# FPGA_USB.net
KiCad netlist of a schematic drawn in Altium Designer
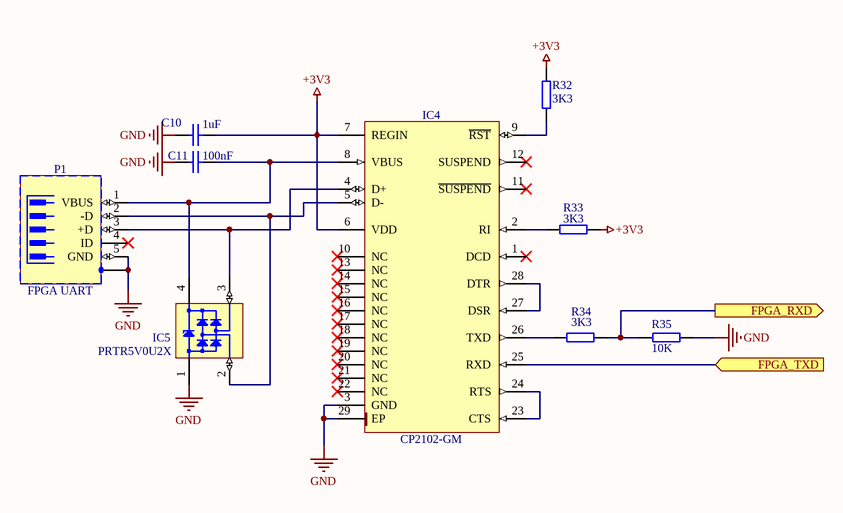
[diagram p0: FPGA_USB.SchDoc]

(export (version "E")
  (design (tool "Eeschema 10.0.6"))
  (components
    (comp (ref "C10")
      (value "1uF")
      (footprint "CC1608-0603")
      (description "Capacitor")
      (fields
        (field (name "TOLERANCE") "±10%")
        (field (name "VOLTAGE") "25V")
        (field (name "PUBLISHER") "Altium Limited")
      )
      (libsource (lib "wr_switch") (part "Cap"))
    )
    (comp (ref "C11")
      (value "100nF")
      (footprint "CC1608-0603")
      (description "Capacitor")
      (fields
        (field (name "TOLERANCE") "±10%")
        (field (name "VOLTAGE") "16V")
        (field (name "PUBLISHER") "Altium Limited")
      )
      (libsource (lib "wr_switch") (part "Cap"))
    )
    (comp (ref "IC4")
      (value "CP2102-GM")
      (footprint "7S_WR:QFN50P500X500X100-29N-S335")
      (description "Single-Chip USB to UART Bridge")
      (fields (field (name "MANUFACTURER") "SILICON LABS") (field (name "AUTHOR") "CERN DEM JLC"))
      (libsource (lib "wr_switch") (part "CP2102-GM"))
    )
    (comp (ref "IC5")
      (value "PRTR5V0U2X")
      (footprint "7S_WR:SOT190P230X110-4N")
      (description "Ultra Low Capacitance Double Rail-to-Rail ESD Protection Diode")
      (fields
        (field (name "VOLTAGE") "5.5V")
        (field (name "MANUFACTURER") "PHILIPS NXP")
        (field (name "AUTHOR") "CERN DEM JLC")
      )
      (libsource (lib "wr_switch") (part "PRTR5V0U2X"))
    )
    (comp (ref "P1")
      (value "FPGA UART")
      (footprint "7S_WR:TYCO_1734035-1")
      (description "5 Pin + 1 Shield Mini USB Type B Receptacle")
      (fields
        (field (name "PART NUMBER") "TYCO_1734035-1")
        (field (name "MANUFACTURER") "TYCO ELECTRONICS")
        (field (name "AUTHOR") "CERN DEM JLC")
      )
      (libsource (lib "wr_switch") (part "TYCO_1734035-1"))
    )
    (comp (ref "R32")
      (value "3K3")
      (footprint "0603")
      (description "SMD Resistor")
      (fields (field (name "TOLERANCE") "±1%"))
      (libsource (lib "wr_switch") (part "RES_SMD"))
    )
    (comp (ref "R33")
      (value "3K3")
      (footprint "0603")
      (description "SMD Resistor")
      (fields (field (name "TOLERANCE") "±1%"))
      (libsource (lib "wr_switch") (part "RES_SMD"))
    )
    (comp (ref "R34")
      (value "3K3")
      (footprint "0603")
      (description "SMD Resistor")
      (fields (field (name "TOLERANCE") "±1%"))
      (libsource (lib "wr_switch") (part "RES_SMD"))
    )
    (comp (ref "R35")
      (value "10K")
      (footprint "0603")
      (description "SMD Resistor")
      (fields (field (name "TOLERANCE") "±1%"))
      (libsource (lib "wr_switch") (part "RES_SMD"))
    )
  )
  (nets
    (net (code "1") (name "+3V3") (class "Default")
      (node (ref "C10") (pin "2") (pinfunction "2_2") (pintype "passive"))
      (node (ref "IC4") (pin "6") (pinfunction "VDD_6") (pintype "power_in"))
      (node (ref "IC4") (pin "7") (pinfunction "REGIN_7") (pintype "power_in"))
      (node (ref "R32") (pin "2") (pinfunction "2_2") (pintype "passive"))
      (node (ref "R33") (pin "2") (pinfunction "2_2") (pintype "passive"))
    )
    (net (code "2") (name "/FPGA_RXD") (class "Default")
      (node (ref "R34") (pin "2") (pinfunction "2_2") (pintype "passive"))
      (node (ref "R35") (pin "2") (pinfunction "2_2") (pintype "passive"))
    )
    (net (code "3") (name "/FPGA_TXD") (class "Default")
      (node (ref "IC4") (pin "25") (pinfunction "RXD_25") (pintype "input"))
    )
    (net (code "4") (name "GND") (class "Default")
      (node (ref "C10") (pin "1") (pinfunction "1_1") (pintype "passive"))
      (node (ref "C11") (pin "2") (pinfunction "2_2") (pintype "passive"))
      (node (ref "IC4") (pin "29") (pinfunction "EP_29") (pintype "power_in"))
      (node (ref "IC4") (pin "3") (pinfunction "GND_3") (pintype "power_in"))
      (node (ref "IC5") (pin "1") (pinfunction "GND_1") (pintype "power_in"))
      (node (ref "P1") (pin "5") (pinfunction "GND_5") (pintype "bidirectional"))
      (node (ref "P1") (pin "6") (pinfunction "SH_6") (pintype "power_in"))
      (node (ref "R35") (pin "1") (pinfunction "1_1") (pintype "passive"))
    )
    (net (code "5") (name "Net-(IC4-CTS)") (class "Default")
      (node (ref "IC4") (pin "23") (pinfunction "CTS_23") (pintype "input"))
      (node (ref "IC4") (pin "24") (pinfunction "RTS_24") (pintype "output"))
    )
    (net (code "6") (name "Net-(IC4-D+)") (class "Default")
      (node (ref "IC4") (pin "4") (pinfunction "D+_4") (pintype "bidirectional"))
      (node (ref "IC5") (pin "3") (pinfunction "I/O2_3") (pintype "bidirectional"))
      (node (ref "P1") (pin "3") (pinfunction "+D_3") (pintype "bidirectional"))
    )
    (net (code "7") (name "Net-(IC4-D-)") (class "Default")
      (node (ref "IC4") (pin "5") (pinfunction "D-_5") (pintype "bidirectional"))
      (node (ref "IC5") (pin "2") (pinfunction "I/O1_2") (pintype "bidirectional"))
      (node (ref "P1") (pin "2") (pinfunction "-D_2") (pintype "bidirectional"))
    )
    (net (code "8") (name "Net-(IC4-DSR)") (class "Default")
      (node (ref "IC4") (pin "27") (pinfunction "DSR_27") (pintype "input"))
      (node (ref "IC4") (pin "28") (pinfunction "DTR_28") (pintype "output"))
    )
    (net (code "9") (name "Net-(IC4-RI)") (class "Default")
      (node (ref "IC4") (pin "2") (pinfunction "RI_2") (pintype "input"))
      (node (ref "R33") (pin "1") (pinfunction "1_1") (pintype "passive"))
    )
    (net (code "10") (name "Net-(IC4-TXD)") (class "Default")
      (node (ref "IC4") (pin "26") (pinfunction "TXD_26") (pintype "output"))
      (node (ref "R34") (pin "1") (pinfunction "1_1") (pintype "passive"))
    )
    (net (code "11") (name "Net-(IC4-VBUS)") (class "Default")
      (node (ref "C11") (pin "1") (pinfunction "1_1") (pintype "passive"))
      (node (ref "IC4") (pin "8") (pinfunction "VBUS_8") (pintype "input"))
      (node (ref "IC5") (pin "4") (pinfunction "VCC_4") (pintype "power_in"))
      (node (ref "P1") (pin "1") (pinfunction "VBUS_1") (pintype "bidirectional"))
    )
    (net (code "12") (name "Net-(IC4-~{RST})") (class "Default")
      (node (ref "IC4") (pin "9") (pinfunction "~{RST}_9") (pintype "bidirectional"))
      (node (ref "R32") (pin "1") (pinfunction "1_1") (pintype "passive"))
    )
    (net (code "13") (name "unconnected-(IC4-DCD-Pad1)") (class "Default")
      (node (ref "IC4") (pin "1") (pinfunction "DCD_1") (pintype "input+no_connect"))
    )
    (net (code "14") (name "unconnected-(IC4-NC-Pad10)") (class "Default")
      (node (ref "IC4") (pin "10") (pinfunction "NC_10") (pintype "passive+no_connect"))
    )
    (net (code "15") (name "unconnected-(IC4-NC-Pad13)") (class "Default")
      (node (ref "IC4") (pin "13") (pinfunction "NC_13") (pintype "passive+no_connect"))
    )
    (net (code "16") (name "unconnected-(IC4-NC-Pad14)") (class "Default")
      (node (ref "IC4") (pin "14") (pinfunction "NC_14") (pintype "passive+no_connect"))
    )
    (net (code "17") (name "unconnected-(IC4-NC-Pad15)") (class "Default")
      (node (ref "IC4") (pin "15") (pinfunction "NC_15") (pintype "passive+no_connect"))
    )
    (net (code "18") (name "unconnected-(IC4-NC-Pad16)") (class "Default")
      (node (ref "IC4") (pin "16") (pinfunction "NC_16") (pintype "passive+no_connect"))
    )
    (net (code "19") (name "unconnected-(IC4-NC-Pad17)") (class "Default")
      (node (ref "IC4") (pin "17") (pinfunction "NC_17") (pintype "passive+no_connect"))
    )
    (net (code "20") (name "unconnected-(IC4-NC-Pad18)") (class "Default")
      (node (ref "IC4") (pin "18") (pinfunction "NC_18") (pintype "passive+no_connect"))
    )
    (net (code "21") (name "unconnected-(IC4-NC-Pad19)") (class "Default")
      (node (ref "IC4") (pin "19") (pinfunction "NC_19") (pintype "passive+no_connect"))
    )
    (net (code "22") (name "unconnected-(IC4-NC-Pad20)") (class "Default")
      (node (ref "IC4") (pin "20") (pinfunction "NC_20") (pintype "passive+no_connect"))
    )
    (net (code "23") (name "unconnected-(IC4-NC-Pad21)") (class "Default")
      (node (ref "IC4") (pin "21") (pinfunction "NC_21") (pintype "passive+no_connect"))
    )
    (net (code "24") (name "unconnected-(IC4-NC-Pad22)") (class "Default")
      (node (ref "IC4") (pin "22") (pinfunction "NC_22") (pintype "passive+no_connect"))
    )
    (net (code "25") (name "unconnected-(IC4-SUSPEND-Pad12)") (class "Default")
      (node (ref "IC4") (pin "12") (pinfunction "SUSPEND_12") (pintype "output+no_connect"))
    )
    (net (code "26") (name "unconnected-(IC4-~{SUSPEND}-Pad11)") (class "Default")
      (node (ref "IC4") (pin "11") (pinfunction "~{SUSPEND}_11") (pintype "output+no_connect"))
    )
    (net (code "27") (name "unconnected-(P1-ID-Pad4)") (class "Default")
      (node (ref "P1") (pin "4") (pinfunction "ID_4") (pintype "passive+no_connect"))
    )
  )
)
